# phantom_preamp.net
KiCad netlist of a schematic drawn in EAGLE
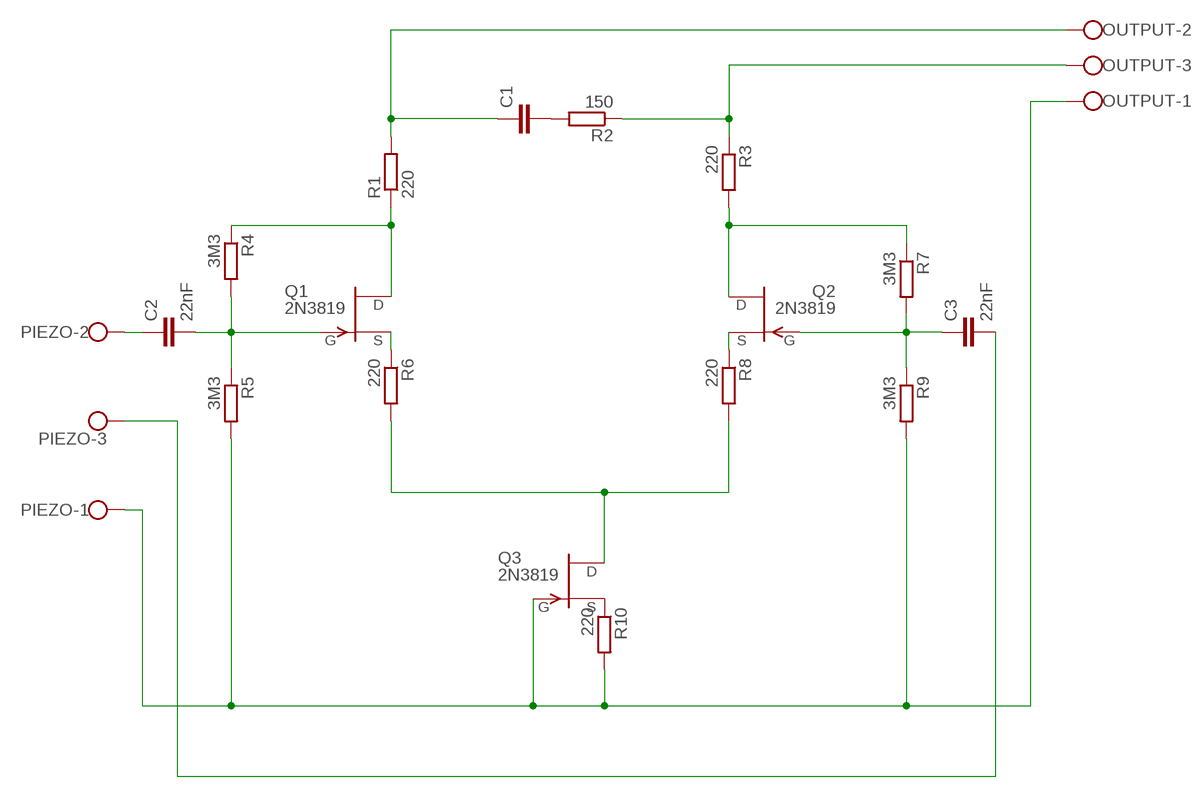
[diagram p0: schematic, sheet 1]

(export (version "E")
  (design (tool "Eeschema 10.0.6"))
  (components
    (comp (ref "C1")
      (value "C-EU050-024X044")
      (footprint "eagle-import:C050-024X044")
      (libsource (lib "eagle-import") (part "C-EU050-024X044"))
    )
    (comp (ref "C2")
      (value "22nF")
      (footprint "eagle-import:C050-024X044")
      (libsource (lib "eagle-import") (part "C-EU050-024X044"))
    )
    (comp (ref "C3")
      (value "22nF")
      (footprint "eagle-import:C050-024X044")
      (libsource (lib "eagle-import") (part "C-EU050-024X044"))
    )
    (comp (ref "OUTPUT")
      (value "W237-103")
      (footprint "eagle-import:W237-103")
      (fields (field (name "MPN") "237-103"))
      (libsource (lib "eagle-import") (part "W237-103"))
    )
    (comp (ref "PIEZO")
      (value "W237-103")
      (footprint "eagle-import:W237-103")
      (fields (field (name "MPN") "237-103"))
      (libsource (lib "eagle-import") (part "W237-103"))
    )
    (comp (ref "Q1")
      (value "2N3819")
      (footprint "eagle-import:TO92")
      (libsource (lib "eagle-import") (part "2N3819"))
    )
    (comp (ref "Q2")
      (value "2N3819")
      (footprint "eagle-import:TO92")
      (libsource (lib "eagle-import") (part "2N3819"))
    )
    (comp (ref "Q3")
      (value "2N3819")
      (footprint "eagle-import:TO92")
      (libsource (lib "eagle-import") (part "2N3819"))
    )
    (comp (ref "R1")
      (value "220")
      (footprint "eagle-import:0207_2V")
      (libsource (lib "eagle-import") (part "R-EU_0207/2V"))
    )
    (comp (ref "R2")
      (value "150")
      (footprint "eagle-import:0207_2V")
      (libsource (lib "eagle-import") (part "R-EU_0207/2V"))
    )
    (comp (ref "R3")
      (value "220")
      (footprint "eagle-import:0207_2V")
      (libsource (lib "eagle-import") (part "R-EU_0207/2V"))
    )
    (comp (ref "R4")
      (value "3M3")
      (footprint "eagle-import:0207_2V")
      (libsource (lib "eagle-import") (part "R-EU_0207/2V"))
    )
    (comp (ref "R5")
      (value "3M3")
      (footprint "eagle-import:0207_2V")
      (libsource (lib "eagle-import") (part "R-EU_0207/2V"))
    )
    (comp (ref "R6")
      (value "220")
      (footprint "eagle-import:0207_2V")
      (libsource (lib "eagle-import") (part "R-EU_0207/2V"))
    )
    (comp (ref "R7")
      (value "3M3")
      (footprint "eagle-import:0207_2V")
      (libsource (lib "eagle-import") (part "R-EU_0207/2V"))
    )
    (comp (ref "R8")
      (value "220")
      (footprint "eagle-import:0207_2V")
      (libsource (lib "eagle-import") (part "R-EU_0207/2V"))
    )
    (comp (ref "R9")
      (value "3M3")
      (footprint "eagle-import:0207_2V")
      (libsource (lib "eagle-import") (part "R-EU_0207/2V"))
    )
    (comp (ref "R10")
      (value "220")
      (footprint "eagle-import:0207_2V")
      (libsource (lib "eagle-import") (part "R-EU_0207/2V"))
    )
  )
  (nets
    (net (code "1") (name "Net-(C1-Pad2)") (class "Default")
      (node (ref "C1") (pin "2") (pinfunction "2_2") (pintype "passive"))
      (node (ref "R2") (pin "2") (pinfunction "2_2") (pintype "passive"))
    )
    (net (code "2") (name "Net-(OUTPUTA-KL)") (class "Default")
      (node (ref "OUTPUT") (pin "1") (pinfunction "KL_1") (pintype "passive"))
      (node (ref "PIEZO") (pin "1") (pinfunction "KL_1") (pintype "passive"))
      (node (ref "Q3") (pin "2") (pinfunction "G_2") (pintype "passive"))
      (node (ref "R10") (pin "2") (pinfunction "2_2") (pintype "passive"))
      (node (ref "R5") (pin "2") (pinfunction "2_2") (pintype "passive"))
      (node (ref "R9") (pin "2") (pinfunction "2_2") (pintype "passive"))
    )
    (net (code "3") (name "Net-(OUTPUTB-KL)") (class "Default")
      (node (ref "C1") (pin "1") (pinfunction "1_1") (pintype "passive"))
      (node (ref "OUTPUT") (pin "2") (pinfunction "KL_2") (pintype "passive"))
      (node (ref "R1") (pin "2") (pinfunction "2_2") (pintype "passive"))
    )
    (net (code "4") (name "Net-(OUTPUTC-KL)") (class "Default")
      (node (ref "OUTPUT") (pin "3") (pinfunction "KL_3") (pintype "passive"))
      (node (ref "R2") (pin "1") (pinfunction "1_1") (pintype "passive"))
      (node (ref "R3") (pin "1") (pinfunction "1_1") (pintype "passive"))
    )
    (net (code "5") (name "Net-(PIEZOB-KL)") (class "Default")
      (node (ref "C2") (pin "1") (pinfunction "1_1") (pintype "passive"))
      (node (ref "PIEZO") (pin "2") (pinfunction "KL_2") (pintype "passive"))
    )
    (net (code "6") (name "Net-(PIEZOC-KL)") (class "Default")
      (node (ref "C3") (pin "2") (pinfunction "2_2") (pintype "passive"))
      (node (ref "PIEZO") (pin "3") (pinfunction "KL_3") (pintype "passive"))
    )
    (net (code "7") (name "Net-(Q1-D)") (class "Default")
      (node (ref "Q1") (pin "1") (pinfunction "D_1") (pintype "passive"))
      (node (ref "R1") (pin "1") (pinfunction "1_1") (pintype "passive"))
      (node (ref "R4") (pin "1") (pinfunction "1_1") (pintype "passive"))
    )
    (net (code "8") (name "Net-(Q1-G)") (class "Default")
      (node (ref "C2") (pin "2") (pinfunction "2_2") (pintype "passive"))
      (node (ref "Q1") (pin "2") (pinfunction "G_2") (pintype "passive"))
      (node (ref "R4") (pin "2") (pinfunction "2_2") (pintype "passive"))
      (node (ref "R5") (pin "1") (pinfunction "1_1") (pintype "passive"))
    )
    (net (code "9") (name "Net-(Q1-S)") (class "Default")
      (node (ref "Q1") (pin "3") (pinfunction "S_3") (pintype "passive"))
      (node (ref "R6") (pin "1") (pinfunction "1_1") (pintype "passive"))
    )
    (net (code "10") (name "Net-(Q2-D)") (class "Default")
      (node (ref "Q2") (pin "1") (pinfunction "D_1") (pintype "passive"))
      (node (ref "R3") (pin "2") (pinfunction "2_2") (pintype "passive"))
      (node (ref "R7") (pin "1") (pinfunction "1_1") (pintype "passive"))
    )
    (net (code "11") (name "Net-(Q2-G)") (class "Default")
      (node (ref "C3") (pin "1") (pinfunction "1_1") (pintype "passive"))
      (node (ref "Q2") (pin "2") (pinfunction "G_2") (pintype "passive"))
      (node (ref "R7") (pin "2") (pinfunction "2_2") (pintype "passive"))
      (node (ref "R9") (pin "1") (pinfunction "1_1") (pintype "passive"))
    )
    (net (code "12") (name "Net-(Q2-S)") (class "Default")
      (node (ref "Q2") (pin "3") (pinfunction "S_3") (pintype "passive"))
      (node (ref "R8") (pin "1") (pinfunction "1_1") (pintype "passive"))
    )
    (net (code "13") (name "Net-(Q3-D)") (class "Default")
      (node (ref "Q3") (pin "1") (pinfunction "D_1") (pintype "passive"))
      (node (ref "R6") (pin "2") (pinfunction "2_2") (pintype "passive"))
      (node (ref "R8") (pin "2") (pinfunction "2_2") (pintype "passive"))
    )
    (net (code "14") (name "Net-(Q3-S)") (class "Default")
      (node (ref "Q3") (pin "3") (pinfunction "S_3") (pintype "passive"))
      (node (ref "R10") (pin "1") (pinfunction "1_1") (pintype "passive"))
    )
  )
)
